# 03_BLBB_Peripheral.net
KiCad netlist of a schematic drawn in Altium Designer
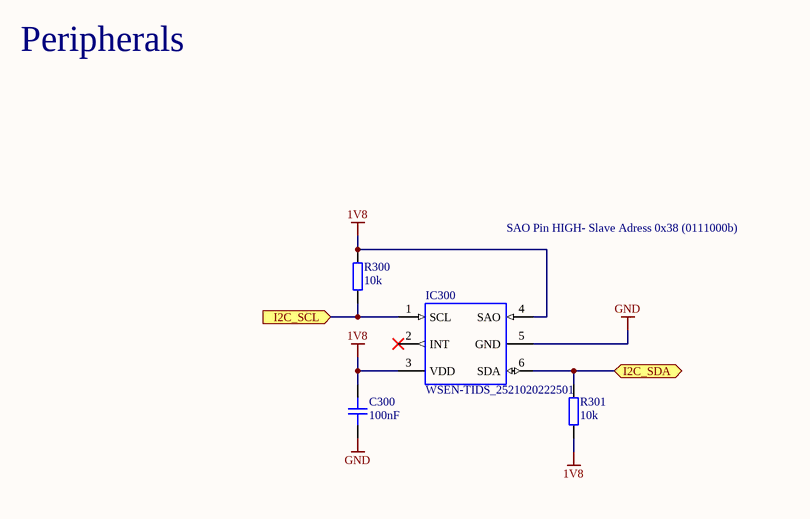
[diagram p0: 03_BLBB_Peripheral.SchDoc]

(export (version "E")
  (design (tool "Eeschema 10.0.6"))
  (components
    (comp (ref "C300")
      (value "100nF")
      (footprint "CAP_0603")
      (description "Capacitor SMD 0603 10V")
      (libsource (lib "Schematic-Lib-PhilsLab") (part "CAP_0603_10V"))
    )
    (comp (ref "IC300")
      (value "WSEN-TIDS_2521020222501")
      (footprint "WSEN-TIDS_2521020222501")
      (fields (field (name "MANUFACTURER") "Würth Elektronik"))
      (libsource (lib "WE_WSEN-REV4.1") (part "WSEN-TIDS_2521020222501"))
    )
    (comp (ref "R300")
      (value "10k")
      (footprint "RES_0603")
      (description "Resistor SMD 0603")
      (libsource (lib "Schematic-Lib-PhilsLab") (part "RES_0603"))
    )
    (comp (ref "R301")
      (value "10k")
      (footprint "RES_0603")
      (description "Resistor SMD 0603")
      (libsource (lib "Schematic-Lib-PhilsLab") (part "RES_0603"))
    )
  )
  (nets
    (net (code "1") (name "/I2C_SCL") (class "Default")
      (node (ref "IC300") (pin "1") (pinfunction "SCL_1") (pintype "input"))
      (node (ref "R300") (pin "1") (pinfunction "1_1") (pintype "passive"))
    )
    (net (code "2") (name "/I2C_SDA") (class "Default")
      (node (ref "IC300") (pin "6") (pinfunction "SDA_6") (pintype "bidirectional"))
      (node (ref "R301") (pin "2") (pinfunction "2_2") (pintype "passive"))
    )
    (net (code "3") (name "1V8") (class "Default")
      (node (ref "C300") (pin "2") (pinfunction "2_2") (pintype "passive"))
      (node (ref "IC300") (pin "3") (pinfunction "VDD_3") (pintype "power_in"))
      (node (ref "IC300") (pin "4") (pinfunction "SAO_4") (pintype "input"))
      (node (ref "R300") (pin "2") (pinfunction "2_2") (pintype "passive"))
      (node (ref "R301") (pin "1") (pinfunction "1_1") (pintype "passive"))
    )
    (net (code "4") (name "GND") (class "Default")
      (node (ref "C300") (pin "1") (pinfunction "1_1") (pintype "passive"))
      (node (ref "IC300") (pin "5") (pinfunction "GND_5") (pintype "power_in"))
    )
    (net (code "5") (name "unconnected-(IC300-INT-Pad2)") (class "Default")
      (node (ref "IC300") (pin "2") (pinfunction "INT_2") (pintype "output+no_connect"))
    )
  )
)
